# BLERADAR-V12.net
KiCad netlist of a schematic drawn in Altium Designer
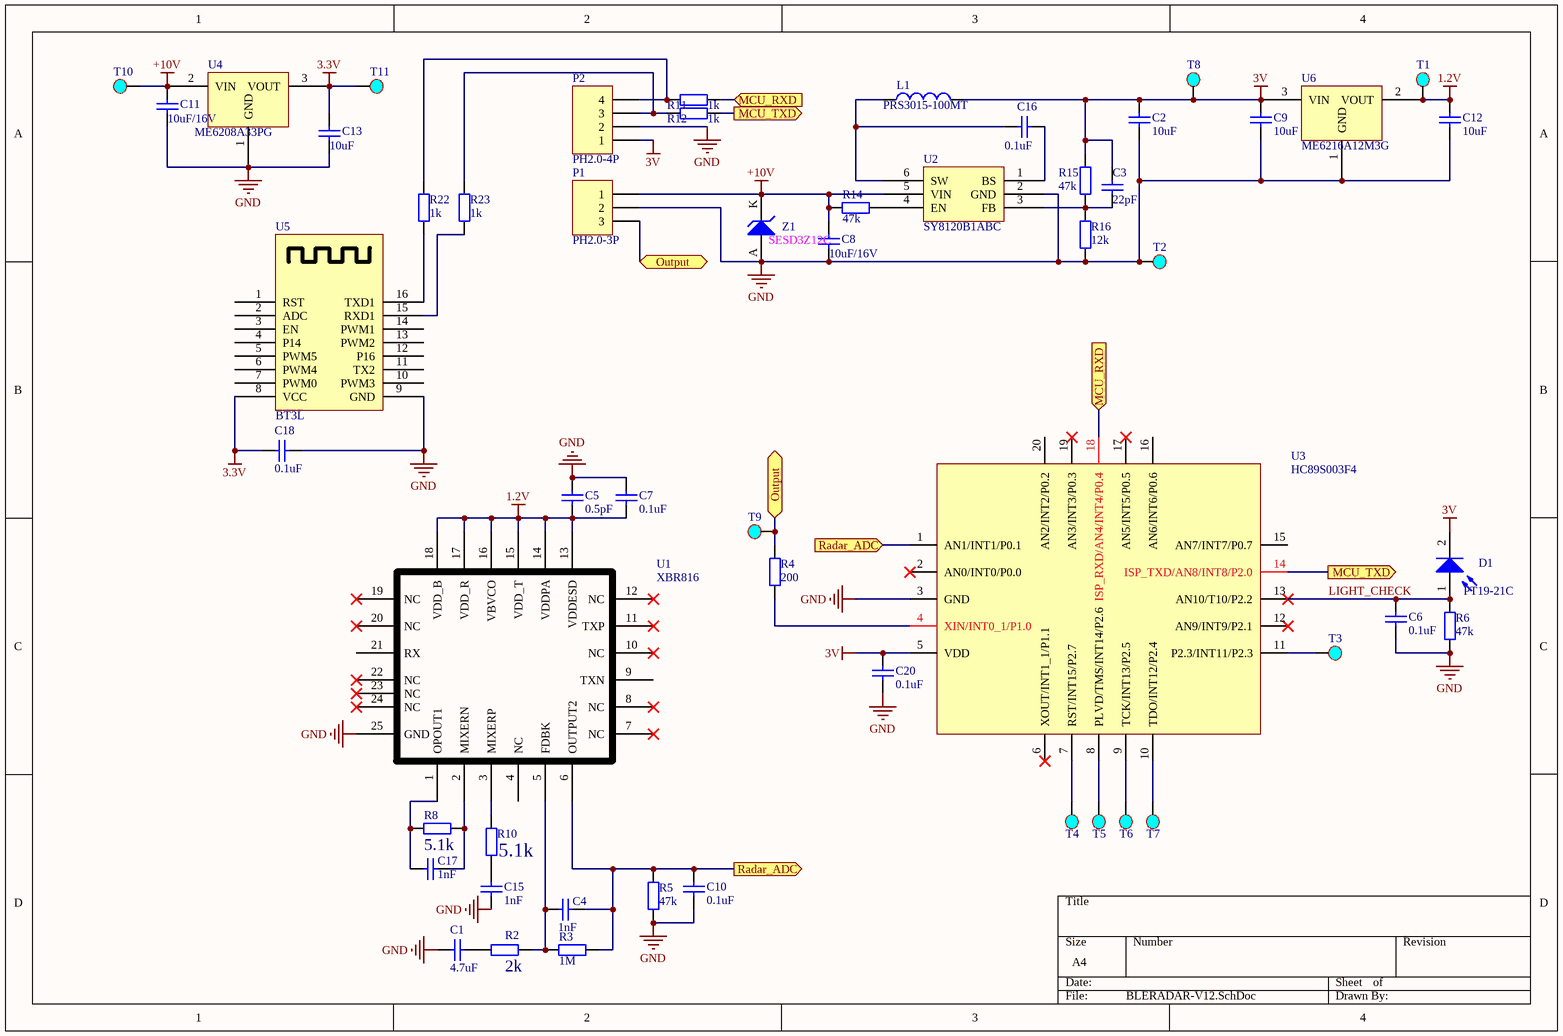
[diagram p0: BLERADAR-V12.SchDoc]

(export (version "E")
  (design (tool "Eeschema 10.0.6"))
  (components
    (comp (ref "C1")
      (value "4.7uF")
      (footprint "C0402")
      (description "Capacitor")
      (fields (field (name "PUBLISHER") "Altium Limited"))
      (libsource (lib "Miscellaneous Devices") (part "Cap"))
    )
    (comp (ref "C2")
      (value "10uF")
      (footprint "C0402")
      (description "Capacitor")
      (fields (field (name "PUBLISHER") "Altium Limited"))
      (libsource (lib "Miscellaneous Devices") (part "Cap"))
    )
    (comp (ref "C3")
      (value "22pF")
      (footprint "C0402")
      (description "Capacitor")
      (fields (field (name "PUBLISHER") "Altium Limited"))
      (libsource (lib "Miscellaneous Devices") (part "Cap"))
    )
    (comp (ref "C4")
      (value "1nF")
      (footprint "C0402")
      (description "Capacitor")
      (fields (field (name "PUBLISHER") "Altium Limited"))
      (libsource (lib "Miscellaneous Devices") (part "Cap"))
    )
    (comp (ref "C5")
      (value "0.5pF")
      (footprint "C0402")
      (description "Capacitor")
      (fields (field (name "PUBLISHER") "Altium Limited"))
      (libsource (lib "Miscellaneous Devices") (part "Cap"))
    )
    (comp (ref "C6")
      (value "0.1uF")
      (footprint "C0402")
      (description "Capacitor")
      (fields (field (name "PUBLISHER") "Altium Limited"))
      (libsource (lib "Miscellaneous Devices") (part "Cap"))
    )
    (comp (ref "C7")
      (value "0.1uF")
      (footprint "C0402")
      (description "Capacitor")
      (fields (field (name "PUBLISHER") "Altium Limited"))
      (libsource (lib "Miscellaneous Devices") (part "Cap"))
    )
    (comp (ref "C8")
      (value "10uF/16V")
      (footprint "C0603")
      (description "Capacitor")
      (fields (field (name "PUBLISHER") "Altium Limited"))
      (libsource (lib "Miscellaneous Devices") (part "Cap"))
    )
    (comp (ref "C9")
      (value "10uF")
      (footprint "C0402")
      (description "Capacitor")
      (fields (field (name "PUBLISHER") "Altium Limited"))
      (libsource (lib "Miscellaneous Devices") (part "Cap"))
    )
    (comp (ref "C10")
      (value "0.1uF")
      (footprint "C0402")
      (description "Capacitor")
      (fields (field (name "PUBLISHER") "Altium Limited"))
      (libsource (lib "Miscellaneous Devices") (part "Cap"))
    )
    (comp (ref "C11")
      (value "10uF/16V")
      (footprint "C0603")
      (description "Capacitor")
      (fields (field (name "PUBLISHER") "Altium Limited"))
      (libsource (lib "Miscellaneous Devices") (part "Cap"))
    )
    (comp (ref "C12")
      (value "10uF")
      (footprint "C0402")
      (description "Capacitor")
      (fields (field (name "PUBLISHER") "Altium Limited"))
      (libsource (lib "Miscellaneous Devices") (part "Cap"))
    )
    (comp (ref "C13")
      (value "10uF")
      (footprint "C0402")
      (description "Capacitor")
      (fields (field (name "PUBLISHER") "Altium Limited"))
      (libsource (lib "Miscellaneous Devices") (part "Cap"))
    )
    (comp (ref "C15")
      (value "1nF")
      (footprint "C0402")
      (description "Capacitor")
      (fields (field (name "PUBLISHER") "Altium Limited"))
      (libsource (lib "Miscellaneous Devices") (part "Cap"))
    )
    (comp (ref "C16")
      (value "0.1uF")
      (footprint "C0402")
      (description "Capacitor")
      (fields (field (name "PUBLISHER") "Altium Limited"))
      (libsource (lib "Miscellaneous Devices") (part "Cap"))
    )
    (comp (ref "C17")
      (value "1nF")
      (footprint "C0402")
      (description "Capacitor")
      (fields (field (name "PUBLISHER") "Altium Limited"))
      (libsource (lib "Miscellaneous Devices") (part "Cap"))
    )
    (comp (ref "C18")
      (value "0.1uF")
      (footprint "C0402")
      (description "Capacitor")
      (fields (field (name "PUBLISHER") "Altium Limited"))
      (libsource (lib "Miscellaneous Devices") (part "Cap"))
    )
    (comp (ref "C20")
      (value "0.1uF")
      (footprint "C0402")
      (description "Capacitor")
      (fields (field (name "PUBLISHER") "Altium Limited"))
      (libsource (lib "Miscellaneous Devices") (part "Cap"))
    )
    (comp (ref "D1")
      (value "PT19-21C")
      (footprint "LED-0603")
      (description "Photosensitive Diode")
      (fields (field (name "PUBLISHER") "Altium Limited"))
      (libsource (lib "Miscellaneous Devices") (part "Photo Sen"))
    )
    (comp (ref "L1")
      (value "PRS3015-100MT")
      (footprint "PRS3015")
      (description "Inductor")
      (fields (field (name "PUBLISHER") "Altium Limited"))
      (libsource (lib "Miscellaneous Devices") (part "Inductor"))
    )
    (comp (ref "P1")
      (value "PH2.0-3P")
      (footprint "PH2.0-3P-LTZ")
      (description "Header, 3-Pin")
      (fields (field (name "PUBLISHER") "Altium Limited"))
      (libsource (lib "Miscellaneous Connectors") (part "Header 3"))
    )
    (comp (ref "P2")
      (value "PH2.0-4P")
      (footprint "HDR1X4")
      (description "Header, 4-Pin")
      (fields (field (name "PUBLISHER") "Altium Limited"))
      (libsource (lib "*") (part "Header 4"))
    )
    (comp (ref "R2")
      (value "2k")
      (footprint "R0402")
      (description "Resistor")
      (fields (field (name "PUBLISHER") "Altium Limited"))
      (libsource (lib "") (part "Res2_2"))
    )
    (comp (ref "R3")
      (value "1M")
      (footprint "R0402")
      (description "Resistor")
      (fields (field (name "PUBLISHER") "Altium Limited"))
      (libsource (lib "") (part "Res2_1"))
    )
    (comp (ref "R4")
      (value "200")
      (footprint "R0402")
      (description "Resistor")
      (fields (field (name "PUBLISHER") "Altium Limited"))
      (libsource (lib "") (part "Res2_3"))
    )
    (comp (ref "R5")
      (value "47k")
      (footprint "R0402")
      (description "Resistor")
      (fields (field (name "PUBLISHER") "Altium Limited"))
      (libsource (lib "Miscellaneous Devices") (part "Res2"))
    )
    (comp (ref "R6")
      (value "47k")
      (footprint "R0402")
      (description "Resistor")
      (fields (field (name "PUBLISHER") "Altium Limited"))
      (libsource (lib "Miscellaneous Devices") (part "Res2"))
    )
    (comp (ref "R8")
      (value "5.1k")
      (footprint "R0402")
      (description "Resistor")
      (fields (field (name "PUBLISHER") "Altium Limited"))
      (libsource (lib "") (part "Res2_1"))
    )
    (comp (ref "R10")
      (value "5.1k")
      (footprint "R0402")
      (description "Resistor")
      (fields (field (name "PUBLISHER") "Altium Limited"))
      (libsource (lib "Miscellaneous Devices") (part "Res2"))
    )
    (comp (ref "R11")
      (value "1k")
      (footprint "R0402")
      (description "Resistor")
      (fields (field (name "PUBLISHER") "Altium Limited"))
      (libsource (lib "") (part "Res2_1"))
    )
    (comp (ref "R12")
      (value "1k")
      (footprint "R0402")
      (description "Resistor")
      (fields (field (name "PUBLISHER") "Altium Limited"))
      (libsource (lib "") (part "Res2_1"))
    )
    (comp (ref "R14")
      (value "47k")
      (footprint "R0402")
      (description "Resistor")
      (fields (field (name "PUBLISHER") "Altium Limited"))
      (libsource (lib "") (part "Res2_1"))
    )
    (comp (ref "R15")
      (value "47k")
      (footprint "R0402")
      (description "Resistor")
      (fields (field (name "PUBLISHER") "Altium Limited"))
      (libsource (lib "") (part "Res2_3"))
    )
    (comp (ref "R16")
      (value "12k")
      (footprint "R0402")
      (description "Resistor")
      (fields (field (name "PUBLISHER") "Altium Limited"))
      (libsource (lib "") (part "Res2_3"))
    )
    (comp (ref "R22")
      (value "1k")
      (footprint "R0402")
      (description "Resistor")
      (fields (field (name "PUBLISHER") "Altium Limited"))
      (libsource (lib "Miscellaneous Devices") (part "Res2"))
    )
    (comp (ref "R23")
      (value "1k")
      (footprint "R0402")
      (description "Resistor")
      (fields (field (name "PUBLISHER") "Altium Limited"))
      (libsource (lib "Miscellaneous Devices") (part "Res2"))
    )
    (comp (ref "T1")
      (value "~")
      (footprint "TestPoints")
      (description "TestPoints")
      (libsource (lib "标准原理图库（特种板）") (part "TestPoints"))
    )
    (comp (ref "T2")
      (value "~")
      (footprint "TestPoints")
      (description "TestPoints")
      (libsource (lib "标准原理图库（特种板）") (part "TestPoints"))
    )
    (comp (ref "T3")
      (value "~")
      (footprint "TestPoints")
      (description "TestPoints")
      (libsource (lib "标准原理图库（特种板）") (part "TestPoints"))
    )
    (comp (ref "T4")
      (value "~")
      (footprint "TestPoints")
      (description "TestPoints")
      (libsource (lib "标准原理图库（特种板）") (part "TestPoints"))
    )
    (comp (ref "T5")
      (value "~")
      (footprint "TestPoints")
      (description "TestPoints")
      (libsource (lib "标准原理图库（特种板）") (part "TestPoints"))
    )
    (comp (ref "T6")
      (value "~")
      (footprint "TestPoints")
      (description "TestPoints")
      (libsource (lib "标准原理图库（特种板）") (part "TestPoints"))
    )
    (comp (ref "T7")
      (value "~")
      (footprint "TestPoints")
      (description "TestPoints")
      (libsource (lib "标准原理图库（特种板）") (part "TestPoints"))
    )
    (comp (ref "T8")
      (value "~")
      (footprint "TestPoints")
      (description "TestPoints")
      (libsource (lib "标准原理图库（特种板）") (part "TestPoints"))
    )
    (comp (ref "T9")
      (value "~")
      (footprint "TestPoints")
      (description "TestPoints")
      (libsource (lib "标准原理图库（特种板）") (part "TestPoints"))
    )
    (comp (ref "T10")
      (value "~")
      (footprint "TestPoints")
      (description "TestPoints")
      (libsource (lib "标准原理图库（特种板）") (part "TestPoints"))
    )
    (comp (ref "T11")
      (value "~")
      (footprint "TestPoints")
      (description "TestPoints")
      (libsource (lib "标准原理图库（特种板）") (part "TestPoints"))
    )
    (comp (ref "U1") (value "XBR816") (footprint "XBR816") (libsource (lib "Schlib1") (part "XBR1000_24_1")))
    (comp (ref "U2") (value "SY8120B1ABC") (footprint "SOT-23-6") (libsource (lib "Schlib1") (part "H9108")))
    (comp (ref "U3")
      (value "HC89S003F4")
      (footprint "QFN20(3*3)")
      (description "MCU")
      (libsource (lib "标准原理图库（特种板）") (part "HC89S003F4"))
    )
    (comp (ref "U4")
      (value "ME6208A33PG")
      (footprint "My Footprint View:SOT89N")
      (libsource (lib "Schlib1") (part "ME6208A50PG"))
    )
    (comp (ref "U5") (value "BT3L") (footprint "ZS3L") (libsource (lib "Schlib-BLE") (part "BT3L")))
    (comp (ref "U6")
      (value "ME6216A12M3G")
      (footprint "SOT-23-L")
      (libsource (lib "Schlib1") (part "SSP6206"))
    )
    (comp (ref "Z1")
      (value "SESD3Z12C")
      (footprint "SOD323")
      (description "Zener Diode")
      (fields (field (name "PUBLISHER") "Altium Limited"))
      (libsource (lib "Miscellaneous Devices") (part "D Zener"))
    )
  )
  (nets
    (net (code "1") (name "+10V") (class "Default")
      (node (ref "C11") (pin "1") (pinfunction "1_1") (pintype "passive"))
      (node (ref "C8") (pin "1") (pinfunction "1_1") (pintype "passive"))
      (node (ref "P1") (pin "1") (pinfunction "1_1") (pintype "passive"))
      (node (ref "R14") (pin "2") (pinfunction "2_2") (pintype "passive"))
      (node (ref "T10") (pin "1") (pinfunction "1_1") (pintype "passive"))
      (node (ref "U2") (pin "5") (pinfunction "VIN_5") (pintype "passive"))
      (node (ref "U4") (pin "2") (pinfunction "VIN_2") (pintype "passive"))
      (node (ref "Z1") (pin "K") (pinfunction "K_K") (pintype "passive"))
    )
    (net (code "2") (name "/LIGHT_CHECK") (class "Default")
      (node (ref "C6") (pin "1") (pinfunction "1_1") (pintype "passive"))
      (node (ref "D1") (pin "1") (pinfunction "A_1") (pintype "passive"))
      (node (ref "R6") (pin "1") (pinfunction "1_1") (pintype "passive"))
      (node (ref "U3") (pin "13") (pinfunction "AN10/T10/P2.2_13") (pintype "passive"))
    )
    (net (code "3") (name "/MCU_RXD") (class "Default")
      (node (ref "R11") (pin "1") (pinfunction "1_1") (pintype "passive"))
      (node (ref "U3") (pin "18") (pinfunction "ISP_RXD/AN4/INT4/P0.4_18") (pintype "passive"))
    )
    (net (code "4") (name "/MCU_TXD") (class "Default")
      (node (ref "R12") (pin "1") (pinfunction "1_1") (pintype "passive"))
      (node (ref "U3") (pin "14") (pinfunction "ISP_TXD/AN8/INT8/P2.0_14") (pintype "passive"))
    )
    (net (code "5") (name "/Output") (class "Default")
      (node (ref "P1") (pin "3") (pinfunction "3_3") (pintype "passive"))
      (node (ref "R4") (pin "2") (pinfunction "2_2") (pintype "passive"))
      (node (ref "T9") (pin "1") (pinfunction "1_1") (pintype "passive"))
    )
    (net (code "6") (name "/Radar_ADC") (class "Default")
      (node (ref "C10") (pin "1") (pinfunction "1_1") (pintype "passive"))
      (node (ref "C4") (pin "1") (pinfunction "1_1") (pintype "passive"))
      (node (ref "R3") (pin "1") (pinfunction "1_1") (pintype "passive"))
      (node (ref "R5") (pin "1") (pinfunction "1_1") (pintype "passive"))
      (node (ref "U1") (pin "6") (pinfunction "OUTPUT2_6") (pintype "passive"))
      (node (ref "U3") (pin "1") (pinfunction "AN1/INT1/P0.1_1") (pintype "passive"))
    )
    (net (code "7") (name "1.2V") (class "Default")
      (node (ref "C12") (pin "1") (pinfunction "1_1") (pintype "passive"))
      (node (ref "C5") (pin "1") (pinfunction "1_1") (pintype "passive"))
      (node (ref "C7") (pin "1") (pinfunction "1_1") (pintype "passive"))
      (node (ref "T1") (pin "1") (pinfunction "1_1") (pintype "passive"))
      (node (ref "U1") (pin "13") (pinfunction "VDDESD_13") (pintype "passive"))
      (node (ref "U1") (pin "14") (pinfunction "VDDPA_14") (pintype "passive"))
      (node (ref "U1") (pin "15") (pinfunction "VDD_T_15") (pintype "passive"))
      (node (ref "U1") (pin "16") (pinfunction "VBVCO_16") (pintype "passive"))
      (node (ref "U1") (pin "17") (pinfunction "VDD_R_17") (pintype "passive"))
      (node (ref "U1") (pin "18") (pinfunction "VDD_B_18") (pintype "passive"))
      (node (ref "U6") (pin "2") (pinfunction "VOUT_2") (pintype "passive"))
    )
    (net (code "8") (name "3.3V") (class "Default")
      (node (ref "C13") (pin "1") (pinfunction "1_1") (pintype "passive"))
      (node (ref "C18") (pin "1") (pinfunction "1_1") (pintype "passive"))
      (node (ref "T11") (pin "1") (pinfunction "1_1") (pintype "passive"))
      (node (ref "U4") (pin "3") (pinfunction "VOUT_3") (pintype "passive"))
      (node (ref "U5") (pin "8") (pinfunction "VCC_8") (pintype "passive"))
    )
    (net (code "9") (name "3V") (class "Default")
      (node (ref "C2") (pin "1") (pinfunction "1_1") (pintype "passive"))
      (node (ref "C20") (pin "2") (pinfunction "2_2") (pintype "passive"))
      (node (ref "C3") (pin "2") (pinfunction "2_2") (pintype "passive"))
      (node (ref "C9") (pin "1") (pinfunction "1_1") (pintype "passive"))
      (node (ref "D1") (pin "2") (pinfunction "K_2") (pintype "passive"))
      (node (ref "L1") (pin "2") (pinfunction "2_2") (pintype "passive"))
      (node (ref "P2") (pin "1") (pinfunction "1_1") (pintype "passive"))
      (node (ref "R15") (pin "2") (pinfunction "2_2") (pintype "passive"))
      (node (ref "T8") (pin "1") (pinfunction "1_1") (pintype "passive"))
      (node (ref "U3") (pin "5") (pinfunction "VDD_5") (pintype "passive"))
      (node (ref "U6") (pin "3") (pinfunction "VIN_3") (pintype "passive"))
    )
    (net (code "10") (name "GND") (class "Default")
      (node (ref "C1") (pin "2") (pinfunction "2_2") (pintype "passive"))
      (node (ref "C10") (pin "2") (pinfunction "2_2") (pintype "passive"))
      (node (ref "C11") (pin "2") (pinfunction "2_2") (pintype "passive"))
      (node (ref "C12") (pin "2") (pinfunction "2_2") (pintype "passive"))
      (node (ref "C13") (pin "2") (pinfunction "2_2") (pintype "passive"))
      (node (ref "C15") (pin "1") (pinfunction "1_1") (pintype "passive"))
      (node (ref "C18") (pin "2") (pinfunction "2_2") (pintype "passive"))
      (node (ref "C2") (pin "2") (pinfunction "2_2") (pintype "passive"))
      (node (ref "C20") (pin "1") (pinfunction "1_1") (pintype "passive"))
      (node (ref "C5") (pin "2") (pinfunction "2_2") (pintype "passive"))
      (node (ref "C6") (pin "2") (pinfunction "2_2") (pintype "passive"))
      (node (ref "C7") (pin "2") (pinfunction "2_2") (pintype "passive"))
      (node (ref "C8") (pin "2") (pinfunction "2_2") (pintype "passive"))
      (node (ref "C9") (pin "2") (pinfunction "2_2") (pintype "passive"))
      (node (ref "P1") (pin "2") (pinfunction "2_2") (pintype "passive"))
      (node (ref "P2") (pin "2") (pinfunction "2_2") (pintype "passive"))
      (node (ref "R16") (pin "1") (pinfunction "1_1") (pintype "passive"))
      (node (ref "R5") (pin "2") (pinfunction "2_2") (pintype "passive"))
      (node (ref "R6") (pin "2") (pinfunction "2_2") (pintype "passive"))
      (node (ref "T2") (pin "1") (pinfunction "1_1") (pintype "passive"))
      (node (ref "U1") (pin "25") (pinfunction "GND_25") (pintype "passive"))
      (node (ref "U2") (pin "2") (pinfunction "GND_2") (pintype "passive"))
      (node (ref "U3") (pin "3") (pinfunction "GND_3") (pintype "passive"))
      (node (ref "U4") (pin "1") (pinfunction "GND_1") (pintype "passive"))
      (node (ref "U5") (pin "9") (pinfunction "GND_9") (pintype "passive"))
      (node (ref "U6") (pin "1") (pinfunction "GND_1") (pintype "passive"))
      (node (ref "Z1") (pin "A") (pinfunction "A_A") (pintype "passive"))
    )
    (net (code "11") (name "Net-(C1-Pad1)") (class "Default")
      (node (ref "C1") (pin "1") (pinfunction "1_1") (pintype "passive"))
      (node (ref "R2") (pin "1") (pinfunction "1_1") (pintype "passive"))
    )
    (net (code "12") (name "Net-(C15-Pad2)") (class "Default")
      (node (ref "C15") (pin "2") (pinfunction "2_2") (pintype "passive"))
      (node (ref "R10") (pin "2") (pinfunction "2_2") (pintype "passive"))
    )
    (net (code "13") (name "Net-(P2-Pad3)") (class "Default")
      (node (ref "P2") (pin "3") (pinfunction "3_3") (pintype "passive"))
      (node (ref "R12") (pin "2") (pinfunction "2_2") (pintype "passive"))
      (node (ref "R23") (pin "1") (pinfunction "1_1") (pintype "passive"))
    )
    (net (code "14") (name "Net-(P2-Pad4)") (class "Default")
      (node (ref "P2") (pin "4") (pinfunction "4_4") (pintype "passive"))
      (node (ref "R11") (pin "2") (pinfunction "2_2") (pintype "passive"))
      (node (ref "R22") (pin "1") (pinfunction "1_1") (pintype "passive"))
    )
    (net (code "15") (name "Net-(U1-FDBK)") (class "Default")
      (node (ref "C4") (pin "2") (pinfunction "2_2") (pintype "passive"))
      (node (ref "R2") (pin "2") (pinfunction "2_2") (pintype "passive"))
      (node (ref "R3") (pin "2") (pinfunction "2_2") (pintype "passive"))
      (node (ref "U1") (pin "5") (pinfunction "FDBK_5") (pintype "passive"))
    )
    (net (code "16") (name "Net-(U1-MIXERN)") (class "Default")
      (node (ref "C17") (pin "1") (pinfunction "1_1") (pintype "passive"))
      (node (ref "R8") (pin "1") (pinfunction "1_1") (pintype "passive"))
      (node (ref "U1") (pin "2") (pinfunction "MIXERN_2") (pintype "passive"))
    )
    (net (code "17") (name "Net-(U1-MIXERP)") (class "Default")
      (node (ref "R10") (pin "1") (pinfunction "1_1") (pintype "passive"))
      (node (ref "U1") (pin "3") (pinfunction "MIXERP_3") (pintype "passive"))
    )
    (net (code "18") (name "Net-(U1-OPOUT1)") (class "Default")
      (node (ref "C17") (pin "2") (pinfunction "2_2") (pintype "passive"))
      (node (ref "R8") (pin "2") (pinfunction "2_2") (pintype "passive"))
      (node (ref "U1") (pin "1") (pinfunction "OPOUT1_1") (pintype "passive"))
    )
    (net (code "19") (name "Net-(U2-BS)") (class "Default")
      (node (ref "C16") (pin "2") (pinfunction "2_2") (pintype "passive"))
      (node (ref "U2") (pin "1") (pinfunction "BS_1") (pintype "passive"))
    )
    (net (code "20") (name "Net-(U2-EN)") (class "Default")
      (node (ref "R14") (pin "1") (pinfunction "1_1") (pintype "passive"))
      (node (ref "U2") (pin "4") (pinfunction "EN_4") (pintype "passive"))
    )
    (net (code "21") (name "Net-(U2-FB)") (class "Default")
      (node (ref "C3") (pin "1") (pinfunction "1_1") (pintype "passive"))
      (node (ref "R15") (pin "1") (pinfunction "1_1") (pintype "passive"))
      (node (ref "R16") (pin "2") (pinfunction "2_2") (pintype "passive"))
      (node (ref "U2") (pin "3") (pinfunction "FB_3") (pintype "passive"))
    )
    (net (code "22") (name "Net-(U2-SW)") (class "Default")
      (node (ref "C16") (pin "1") (pinfunction "1_1") (pintype "passive"))
      (node (ref "L1") (pin "1") (pinfunction "1_1") (pintype "passive"))
      (node (ref "U2") (pin "6") (pinfunction "SW_6") (pintype "passive"))
    )
    (net (code "23") (name "Net-(U3-P2.3{slash}INT11{slash}P2.3)") (class "Default")
      (node (ref "T3") (pin "1") (pinfunction "1_1") (pintype "passive"))
      (node (ref "U3") (pin "11") (pinfunction "P2.3/INT11/P2.3_11") (pintype "passive"))
    )
    (net (code "24") (name "Net-(U3-PLVD{slash}TMS{slash}INT14{slash}P2.6)") (class "Default")
      (node (ref "T5") (pin "1") (pinfunction "1_1") (pintype "passive"))
      (node (ref "U3") (pin "8") (pinfunction "PLVD/TMS/INT14/P2.6_8") (pintype "passive"))
    )
    (net (code "25") (name "Net-(U3-RST{slash}INT15{slash}P2.7)") (class "Default")
      (node (ref "T4") (pin "1") (pinfunction "1_1") (pintype "passive"))
      (node (ref "U3") (pin "7") (pinfunction "RST/INT15/P2.7_7") (pintype "passive"))
    )
    (net (code "26") (name "Net-(U3-TCK{slash}INT13{slash}P2.5)") (class "Default")
      (node (ref "T6") (pin "1") (pinfunction "1_1") (pintype "passive"))
      (node (ref "U3") (pin "9") (pinfunction "TCK/INT13/P2.5_9") (pintype "passive"))
    )
    (net (code "27") (name "Net-(U3-TDO{slash}INT12{slash}P2.4)") (class "Default")
      (node (ref "T7") (pin "1") (pinfunction "1_1") (pintype "passive"))
      (node (ref "U3") (pin "10") (pinfunction "TDO/INT12/P2.4_10") (pintype "passive"))
    )
    (net (code "28") (name "Net-(U3-XIN{slash}INT0_1{slash}P1.0)") (class "Default")
      (node (ref "R4") (pin "1") (pinfunction "1_1") (pintype "passive"))
      (node (ref "U3") (pin "4") (pinfunction "XIN/INT0_1/P1.0_4") (pintype "passive"))
    )
    (net (code "29") (name "Net-(U5-RXD1)") (class "Default")
      (node (ref "R23") (pin "2") (pinfunction "2_2") (pintype "passive"))
      (node (ref "U5") (pin "15") (pinfunction "RXD1_15") (pintype "passive"))
    )
    (net (code "30") (name "Net-(U5-TXD1)") (class "Default")
      (node (ref "R22") (pin "2") (pinfunction "2_2") (pintype "passive"))
      (node (ref "U5") (pin "16") (pinfunction "TXD1_16") (pintype "passive"))
    )
    (net (code "31") (name "unconnected-(U1-NC-Pad4)") (class "Default")
      (node (ref "U1") (pin "4") (pinfunction "NC_4") (pintype "passive"))
    )
    (net (code "32") (name "unconnected-(U1-NC-Pad7)") (class "Default")
      (node (ref "U1") (pin "7") (pinfunction "NC_7") (pintype "passive+no_connect"))
    )
    (net (code "33") (name "unconnected-(U1-NC-Pad8)") (class "Default")
      (node (ref "U1") (pin "8") (pinfunction "NC_8") (pintype "passive+no_connect"))
    )
    (net (code "34") (name "unconnected-(U1-NC-Pad10)") (class "Default")
      (node (ref "U1") (pin "10") (pinfunction "NC_10") (pintype "passive+no_connect"))
    )
    (net (code "35") (name "unconnected-(U1-NC-Pad12)") (class "Default")
      (node (ref "U1") (pin "12") (pinfunction "NC_12") (pintype "passive+no_connect"))
    )
    (net (code "36") (name "unconnected-(U1-NC-Pad19)") (class "Default")
      (node (ref "U1") (pin "19") (pinfunction "NC_19") (pintype "passive+no_connect"))
    )
    (net (code "37") (name "unconnected-(U1-NC-Pad20)") (class "Default")
      (node (ref "U1") (pin "20") (pinfunction "NC_20") (pintype "passive+no_connect"))
    )
    (net (code "38") (name "unconnected-(U1-NC-Pad22)") (class "Default")
      (node (ref "U1") (pin "22") (pinfunction "NC_22") (pintype "passive+no_connect"))
    )
    (net (code "39") (name "unconnected-(U1-NC-Pad23)") (class "Default")
      (node (ref "U1") (pin "23") (pinfunction "NC_23") (pintype "passive+no_connect"))
    )
    (net (code "40") (name "unconnected-(U1-NC-Pad24)") (class "Default")
      (node (ref "U1") (pin "24") (pinfunction "NC_24") (pintype "passive+no_connect"))
    )
    (net (code "41") (name "unconnected-(U1-RX-Pad21)") (class "Default")
      (node (ref "U1") (pin "21") (pinfunction "RX_21") (pintype "passive"))
    )
    (net (code "42") (name "unconnected-(U1-TXN-Pad9)") (class "Default")
      (node (ref "U1") (pin "9") (pinfunction "TXN_9") (pintype "passive"))
    )
    (net (code "43") (name "unconnected-(U1-TXP-Pad11)") (class "Default")
      (node (ref "U1") (pin "11") (pinfunction "TXP_11") (pintype "passive+no_connect"))
    )
    (net (code "44") (name "unconnected-(U3-AN0{slash}INT0{slash}P0.0-Pad2)") (class "Default")
      (node (ref "U3") (pin "2") (pinfunction "AN0/INT0/P0.0_2") (pintype "passive+no_connect"))
    )
    (net (code "45") (name "unconnected-(U3-AN2{slash}INT2{slash}P0.2-Pad20)") (class "Default")
      (node (ref "U3") (pin "20") (pinfunction "AN2/INT2/P0.2_20") (pintype "passive"))
    )
    (net (code "46") (name "unconnected-(U3-AN3{slash}INT3{slash}P0.3-Pad19)") (class "Default")
      (node (ref "U3") (pin "19") (pinfunction "AN3/INT3/P0.3_19") (pintype "passive+no_connect"))
    )
    (net (code "47") (name "unconnected-(U3-AN5{slash}INT5{slash}P0.5-Pad17)") (class "Default")
      (node (ref "U3") (pin "17") (pinfunction "AN5/INT5/P0.5_17") (pintype "passive+no_connect"))
    )
    (net (code "48") (name "unconnected-(U3-AN6{slash}INT6{slash}P0.6-Pad16)") (class "Default")
      (node (ref "U3") (pin "16") (pinfunction "AN6/INT6/P0.6_16") (pintype "passive"))
    )
    (net (code "49") (name "unconnected-(U3-AN7{slash}INT7{slash}P0.7-Pad15)") (class "Default")
      (node (ref "U3") (pin "15") (pinfunction "AN7/INT7/P0.7_15") (pintype "passive"))
    )
    (net (code "50") (name "unconnected-(U3-AN9{slash}INT9{slash}P2.1-Pad12)") (class "Default")
      (node (ref "U3") (pin "12") (pinfunction "AN9/INT9/P2.1_12") (pintype "passive+no_connect"))
    )
    (net (code "51") (name "unconnected-(U3-XOUT{slash}INT1_1{slash}P1.1-Pad6)") (class "Default")
      (node (ref "U3") (pin "6") (pinfunction "XOUT/INT1_1/P1.1_6") (pintype "passive+no_connect"))
    )
    (net (code "52") (name "unconnected-(U5-ADC-Pad2)") (class "Default")
      (node (ref "U5") (pin "2") (pinfunction "ADC_2") (pintype "passive"))
    )
    (net (code "53") (name "unconnected-(U5-EN-Pad3)") (class "Default")
      (node (ref "U5") (pin "3") (pinfunction "EN_3") (pintype "passive"))
    )
    (net (code "54") (name "unconnected-(U5-P14-Pad4)") (class "Default")
      (node (ref "U5") (pin "4") (pinfunction "P14_4") (pintype "passive"))
    )
    (net (code "55") (name "unconnected-(U5-P16-Pad12)") (class "Default")
      (node (ref "U5") (pin "12") (pinfunction "P16_12") (pintype "passive"))
    )
    (net (code "56") (name "unconnected-(U5-PWM0-Pad7)") (class "Default")
      (node (ref "U5") (pin "7") (pinfunction "PWM0_7") (pintype "passive"))
    )
    (net (code "57") (name "unconnected-(U5-PWM1-Pad14)") (class "Default")
      (node (ref "U5") (pin "14") (pinfunction "PWM1_14") (pintype "passive"))
    )
    (net (code "58") (name "unconnected-(U5-PWM2-Pad13)") (class "Default")
      (node (ref "U5") (pin "13") (pinfunction "PWM2_13") (pintype "passive"))
    )
    (net (code "59") (name "unconnected-(U5-PWM3-Pad10)") (class "Default")
      (node (ref "U5") (pin "10") (pinfunction "PWM3_10") (pintype "passive"))
    )
    (net (code "60") (name "unconnected-(U5-PWM4-Pad6)") (class "Default")
      (node (ref "U5") (pin "6") (pinfunction "PWM4_6") (pintype "passive"))
    )
    (net (code "61") (name "unconnected-(U5-PWM5-Pad5)") (class "Default")
      (node (ref "U5") (pin "5") (pinfunction "PWM5_5") (pintype "passive"))
    )
    (net (code "62") (name "unconnected-(U5-RST-Pad1)") (class "Default")
      (node (ref "U5") (pin "1") (pinfunction "RST_1") (pintype "passive"))
    )
    (net (code "63") (name "unconnected-(U5-TX2-Pad11)") (class "Default")
      (node (ref "U5") (pin "11") (pinfunction "TX2_11") (pintype "passive"))
    )
  )
)
